# Memory.net
KiCad netlist of a schematic drawn in Altium Designer
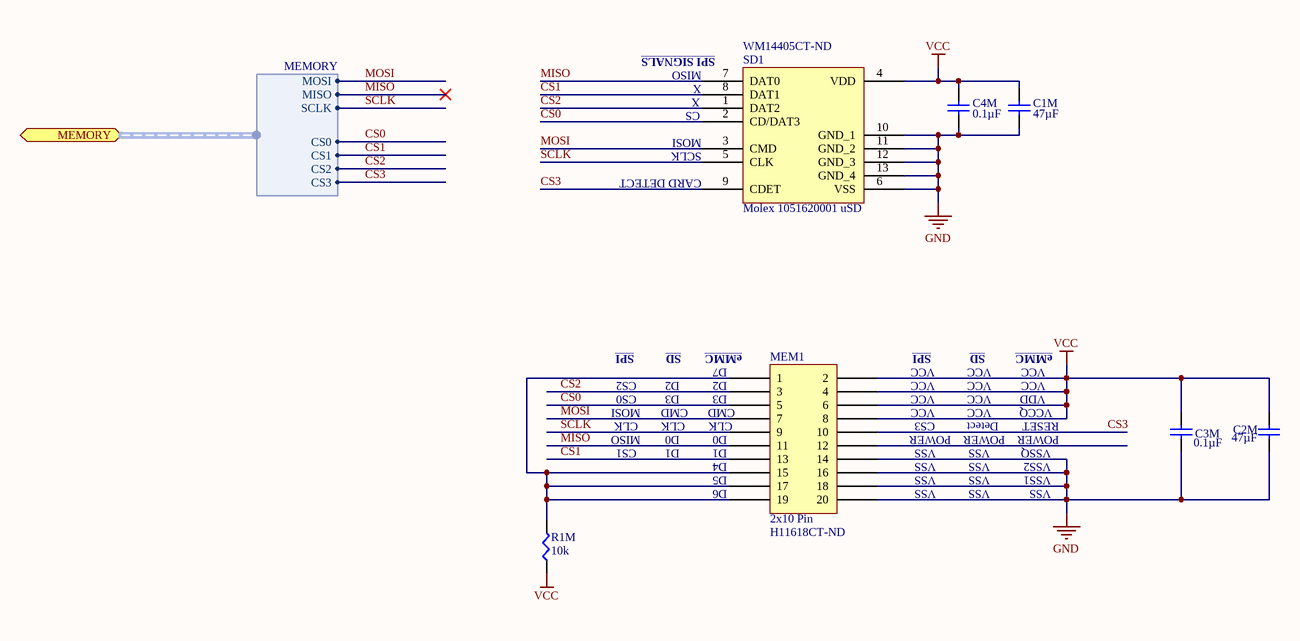
[diagram p0: Memory.SchDoc]

(export (version "E")
  (design (tool "Eeschema 10.0.6"))
  (components
    (comp (ref "C1M")
      (value "GRM21BR61A476ME15L")
      (footprint "C0805N")
      (description "47µF 10V Ceramic Capacitor X5R 0805")
      (fields
        (field (name "HOUSEPART") "NO")
        (field (name "TOLERANCE") "±20%")
        (field (name "CAPACITANCE") "47µF")
      )
      (libsource (lib "MF_Passives") (part "CAPACITOR_NP"))
    )
    (comp (ref "C2M")
      (value "GRM21BR61A476ME15L")
      (footprint "C0805N")
      (description "47µF 10V Ceramic Capacitor X5R 0805")
      (fields
        (field (name "HOUSEPART") "NO")
        (field (name "TOLERANCE") "±20%")
        (field (name "CAPACITANCE") "47µF")
      )
      (libsource (lib "MF_Passives") (part "CAPACITOR_NP"))
    )
    (comp (ref "C3M")
      (value "GCM188R71C104KA37D")
      (footprint "C0603N")
      (fields
        (field (name "HOUSEPART") "NO")
        (field (name "TOLERANCE") "±10%")
        (field (name "VOLTAGE") "16V")
        (field (name "CAPACITANCE") "0.1µF")
      )
      (libsource (lib "MF_Passives") (part "CAPACITOR_NP"))
    )
    (comp (ref "C4M")
      (value "GCM188R71C104KA37D")
      (footprint "C0603N")
      (fields
        (field (name "HOUSEPART") "NO")
        (field (name "TOLERANCE") "±10%")
        (field (name "VOLTAGE") "16V")
        (field (name "CAPACITANCE") "0.1µF")
      )
      (libsource (lib "MF_Passives") (part "CAPACITOR_NP"))
    )
    (comp (ref "MEM1")
      (value "2x10 Pin")
      (footprint "HIROSE DF40C-20DP-N")
      (description "CONN HDR 20POS")
      (fields (field (name "SUPPLIER PART NUMBER 1") "H11618CT-ND"))
      (libsource (lib "Connectors") (part "2x10 Pin"))
    )
    (comp (ref "R1M")
      (value "10k")
      (footprint "SMD-0603-RES")
      (description "RES SMD 10K OHM 1% 1/10W 0603")
      (fields
        (field (name "PART NUMBER") "ERJ-3EKF1002V")
        (field (name "DIGI-KEY PART NUMBER") "P10.0KHCT-ND")
      )
      (libsource (lib "Panasonic_ERJ_0603") (part "ERJ-3EKF1002V"))
    )
    (comp (ref "SD1")
      (value "Molex 1051620001 uSD")
      (footprint "Molex 1051620001")
      (description "1.45H MICRO SD HEADER WITH D/C P")
      (fields (field (name "SUPPLIER PART NUMBER 1") "WM14405CT-ND"))
      (libsource (lib "Connectors") (part "Molex 1051620001 uSD"))
    )
  )
  (nets
    (net (code "2") (name "/CS0") (class "Default")
      (node (ref "MEM1") (pin "5") (pinfunction "5_5") (pintype "passive"))
      (node (ref "SD1") (pin "2") (pinfunction "CD/DAT3_2") (pintype "passive"))
    )
    (net (code "3") (name "/CS1") (class "Default")
      (node (ref "MEM1") (pin "13") (pinfunction "13_13") (pintype "passive"))
      (node (ref "SD1") (pin "8") (pinfunction "DAT1_8") (pintype "passive"))
    )
    (net (code "4") (name "/CS2") (class "Default")
      (node (ref "MEM1") (pin "3") (pinfunction "3_3") (pintype "passive"))
      (node (ref "SD1") (pin "1") (pinfunction "DAT2_1") (pintype "passive"))
    )
    (net (code "5") (name "/CS3") (class "Default")
      (node (ref "MEM1") (pin "10") (pinfunction "10_10") (pintype "passive"))
      (node (ref "SD1") (pin "9") (pinfunction "CDET_9") (pintype "passive"))
    )
    (net (code "6") (name "/MISO") (class "Default")
      (node (ref "MEM1") (pin "11") (pinfunction "11_11") (pintype "passive"))
      (node (ref "SD1") (pin "7") (pinfunction "DAT0_7") (pintype "passive"))
    )
    (net (code "7") (name "/MOSI") (class "Default")
      (node (ref "MEM1") (pin "7") (pinfunction "7_7") (pintype "passive"))
      (node (ref "SD1") (pin "3") (pinfunction "CMD_3") (pintype "passive"))
    )
    (net (code "8") (name "/SCLK") (class "Default")
      (node (ref "MEM1") (pin "9") (pinfunction "9_9") (pintype "passive"))
      (node (ref "SD1") (pin "5") (pinfunction "CLK_5") (pintype "passive"))
    )
    (net (code "10") (name "GND") (class "Default")
      (node (ref "C1M") (pin "1") (pinfunction "1_1") (pintype "passive"))
      (node (ref "C2M") (pin "1") (pinfunction "1_1") (pintype "passive"))
      (node (ref "C3M") (pin "1") (pinfunction "1_1") (pintype "passive"))
      (node (ref "C4M") (pin "1") (pinfunction "1_1") (pintype "passive"))
      (node (ref "MEM1") (pin "14") (pinfunction "14_14") (pintype "passive"))
      (node (ref "MEM1") (pin "16") (pinfunction "16_16") (pintype "passive"))
      (node (ref "MEM1") (pin "18") (pinfunction "18_18") (pintype "passive"))
      (node (ref "MEM1") (pin "20") (pinfunction "20_20") (pintype "passive"))
      (node (ref "SD1") (pin "10") (pinfunction "GND_1_10") (pintype "passive"))
      (node (ref "SD1") (pin "11") (pinfunction "GND_2_11") (pintype "passive"))
      (node (ref "SD1") (pin "12") (pinfunction "GND_3_12") (pintype "passive"))
      (node (ref "SD1") (pin "13") (pinfunction "GND_4_13") (pintype "passive"))
      (node (ref "SD1") (pin "6") (pinfunction "VSS_6") (pintype "passive"))
    )
    (net (code "11") (name "Net-(MEM1-Pad1)") (class "Default")
      (node (ref "MEM1") (pin "1") (pinfunction "1_1") (pintype "passive"))
      (node (ref "MEM1") (pin "15") (pinfunction "15_15") (pintype "passive"))
      (node (ref "MEM1") (pin "17") (pinfunction "17_17") (pintype "passive"))
      (node (ref "MEM1") (pin "19") (pinfunction "19_19") (pintype "passive"))
      (node (ref "R1M") (pin "2") (pinfunction "2_2") (pintype "passive"))
    )
    (net (code "12") (name "VCC") (class "Default")
      (node (ref "C1M") (pin "2") (pinfunction "2_2") (pintype "passive"))
      (node (ref "C2M") (pin "2") (pinfunction "2_2") (pintype "passive"))
      (node (ref "C3M") (pin "2") (pinfunction "2_2") (pintype "passive"))
      (node (ref "C4M") (pin "2") (pinfunction "2_2") (pintype "passive"))
      (node (ref "MEM1") (pin "2") (pinfunction "2_2") (pintype "passive"))
      (node (ref "MEM1") (pin "4") (pinfunction "4_4") (pintype "passive"))
      (node (ref "MEM1") (pin "6") (pinfunction "6_6") (pintype "passive"))
      (node (ref "MEM1") (pin "8") (pinfunction "8_8") (pintype "passive"))
      (node (ref "R1M") (pin "1") (pinfunction "1_1") (pintype "passive"))
      (node (ref "SD1") (pin "4") (pinfunction "VDD_4") (pintype "passive"))
    )
    (net (code "13") (name "unconnected-(MEM1-Pad12)") (class "Default")
      (node (ref "MEM1") (pin "12") (pinfunction "12_12") (pintype "passive"))
    )
  )
)
